# Sensor-Connector.net
KiCad netlist of a schematic drawn in Altium Designer
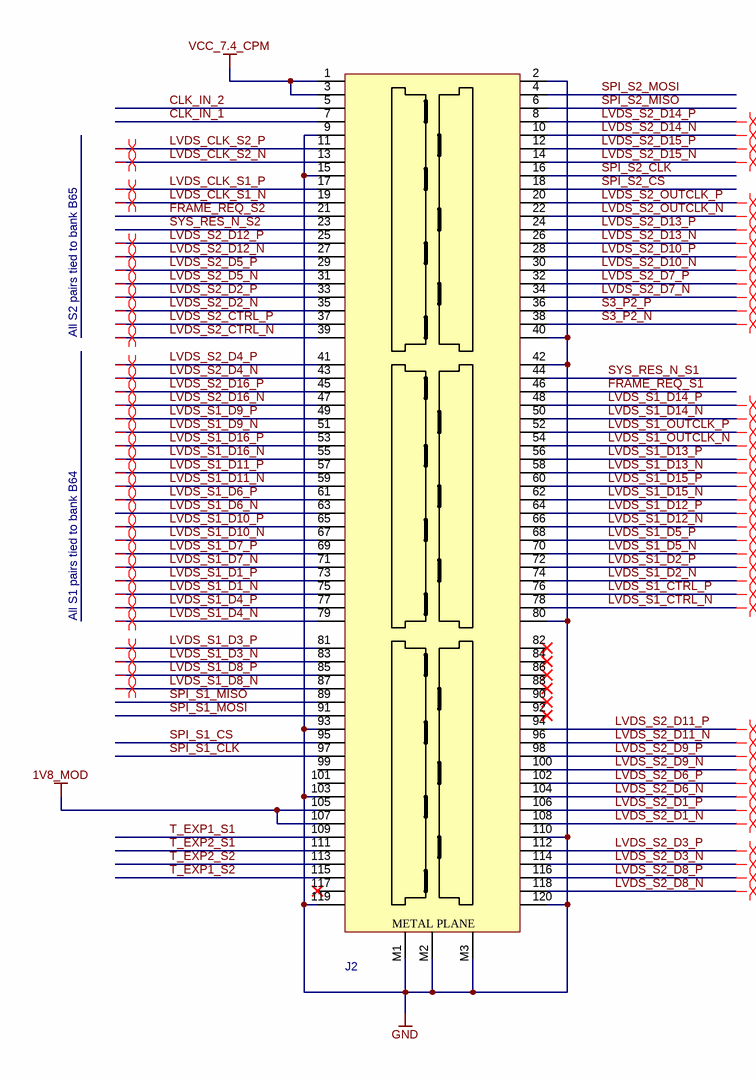
[diagram p0: Sensor-Connector.SchDoc]

(export (version "E")
  (design (tool "Eeschema 10.0.6"))
  (components
    (comp (ref "J2")
      (value "QSE-060-01-L-D-A")
      (footprint "QSE-060-01-L-D-A")
      (fields (field (name "MANUFACTURER") "SAMTEC"))
      (libsource (lib "US-Plus-CPM") (part "QSE-060-01-L-D-A"))
    )
  )
  (nets
    (net (code "1") (name "/CLK_IN_1") (class "Default")
      (node (ref "J2") (pin "7") (pinfunction "7_7") (pintype "passive"))
    )
    (net (code "2") (name "/CLK_IN_2") (class "Default")
      (node (ref "J2") (pin "5") (pinfunction "5_5") (pintype "passive"))
    )
    (net (code "3") (name "/FRAME_REQ_S1") (class "Default")
      (node (ref "J2") (pin "46") (pinfunction "46_46") (pintype "passive"))
    )
    (net (code "4") (name "/FRAME_REQ_S2") (class "Default")
      (node (ref "J2") (pin "21") (pinfunction "21_21") (pintype "passive"))
    )
    (net (code "5") (name "/LVDS_CLK_S1_N") (class "Default")
      (node (ref "J2") (pin "19") (pinfunction "19_19") (pintype "passive"))
    )
    (net (code "6") (name "/LVDS_CLK_S1_P") (class "Default")
      (node (ref "J2") (pin "17") (pinfunction "17_17") (pintype "passive"))
    )
    (net (code "7") (name "/LVDS_CLK_S2_N") (class "Default")
      (node (ref "J2") (pin "13") (pinfunction "13_13") (pintype "passive"))
    )
    (net (code "8") (name "/LVDS_CLK_S2_P") (class "Default")
      (node (ref "J2") (pin "11") (pinfunction "11_11") (pintype "passive"))
    )
    (net (code "9") (name "/LVDS_S1_CTRL_N") (class "Default")
      (node (ref "J2") (pin "78") (pinfunction "78_78") (pintype "passive"))
    )
    (net (code "10") (name "/LVDS_S1_CTRL_P") (class "Default")
      (node (ref "J2") (pin "76") (pinfunction "76_76") (pintype "passive"))
    )
    (net (code "11") (name "/LVDS_S1_D1_N") (class "Default")
      (node (ref "J2") (pin "75") (pinfunction "75_75") (pintype "passive"))
    )
    (net (code "12") (name "/LVDS_S1_D1_P") (class "Default")
      (node (ref "J2") (pin "73") (pinfunction "73_73") (pintype "passive"))
    )
    (net (code "13") (name "/LVDS_S1_D2_N") (class "Default")
      (node (ref "J2") (pin "74") (pinfunction "74_74") (pintype "passive"))
    )
    (net (code "14") (name "/LVDS_S1_D2_P") (class "Default")
      (node (ref "J2") (pin "72") (pinfunction "72_72") (pintype "passive"))
    )
    (net (code "15") (name "/LVDS_S1_D3_N") (class "Default")
      (node (ref "J2") (pin "83") (pinfunction "83_83") (pintype "passive"))
    )
    (net (code "16") (name "/LVDS_S1_D3_P") (class "Default")
      (node (ref "J2") (pin "81") (pinfunction "81_81") (pintype "passive"))
    )
    (net (code "17") (name "/LVDS_S1_D4_N") (class "Default")
      (node (ref "J2") (pin "79") (pinfunction "79_79") (pintype "passive"))
    )
    (net (code "18") (name "/LVDS_S1_D4_P") (class "Default")
      (node (ref "J2") (pin "77") (pinfunction "77_77") (pintype "passive"))
    )
    (net (code "19") (name "/LVDS_S1_D5_N") (class "Default")
      (node (ref "J2") (pin "70") (pinfunction "70_70") (pintype "passive"))
    )
    (net (code "20") (name "/LVDS_S1_D5_P") (class "Default")
      (node (ref "J2") (pin "68") (pinfunction "68_68") (pintype "passive"))
    )
    (net (code "21") (name "/LVDS_S1_D6_N") (class "Default")
      (node (ref "J2") (pin "63") (pinfunction "63_63") (pintype "passive"))
    )
    (net (code "22") (name "/LVDS_S1_D6_P") (class "Default")
      (node (ref "J2") (pin "61") (pinfunction "61_61") (pintype "passive"))
    )
    (net (code "23") (name "/LVDS_S1_D7_N") (class "Default")
      (node (ref "J2") (pin "71") (pinfunction "71_71") (pintype "passive"))
    )
    (net (code "24") (name "/LVDS_S1_D7_P") (class "Default")
      (node (ref "J2") (pin "69") (pinfunction "69_69") (pintype "passive"))
    )
    (net (code "25") (name "/LVDS_S1_D8_N") (class "Default")
      (node (ref "J2") (pin "87") (pinfunction "87_87") (pintype "passive"))
    )
    (net (code "26") (name "/LVDS_S1_D8_P") (class "Default")
      (node (ref "J2") (pin "85") (pinfunction "85_85") (pintype "passive"))
    )
    (net (code "27") (name "/LVDS_S1_D9_N") (class "Default")
      (node (ref "J2") (pin "51") (pinfunction "51_51") (pintype "passive"))
    )
    (net (code "28") (name "/LVDS_S1_D9_P") (class "Default")
      (node (ref "J2") (pin "49") (pinfunction "49_49") (pintype "passive"))
    )
    (net (code "29") (name "/LVDS_S1_D10_N") (class "Default")
      (node (ref "J2") (pin "67") (pinfunction "67_67") (pintype "passive"))
    )
    (net (code "30") (name "/LVDS_S1_D10_P") (class "Default")
      (node (ref "J2") (pin "65") (pinfunction "65_65") (pintype "passive"))
    )
    (net (code "31") (name "/LVDS_S1_D11_N") (class "Default")
      (node (ref "J2") (pin "59") (pinfunction "59_59") (pintype "passive"))
    )
    (net (code "32") (name "/LVDS_S1_D11_P") (class "Default")
      (node (ref "J2") (pin "57") (pinfunction "57_57") (pintype "passive"))
    )
    (net (code "33") (name "/LVDS_S1_D12_N") (class "Default")
      (node (ref "J2") (pin "66") (pinfunction "66_66") (pintype "passive"))
    )
    (net (code "34") (name "/LVDS_S1_D12_P") (class "Default")
      (node (ref "J2") (pin "64") (pinfunction "64_64") (pintype "passive"))
    )
    (net (code "35") (name "/LVDS_S1_D13_N") (class "Default")
      (node (ref "J2") (pin "58") (pinfunction "58_58") (pintype "passive"))
    )
    (net (code "36") (name "/LVDS_S1_D13_P") (class "Default")
      (node (ref "J2") (pin "56") (pinfunction "56_56") (pintype "passive"))
    )
    (net (code "37") (name "/LVDS_S1_D14_N") (class "Default")
      (node (ref "J2") (pin "50") (pinfunction "50_50") (pintype "passive"))
    )
    (net (code "38") (name "/LVDS_S1_D14_P") (class "Default")
      (node (ref "J2") (pin "48") (pinfunction "48_48") (pintype "passive"))
    )
    (net (code "39") (name "/LVDS_S1_D15_N") (class "Default")
      (node (ref "J2") (pin "62") (pinfunction "62_62") (pintype "passive"))
    )
    (net (code "40") (name "/LVDS_S1_D15_P") (class "Default")
      (node (ref "J2") (pin "60") (pinfunction "60_60") (pintype "passive"))
    )
    (net (code "41") (name "/LVDS_S1_D16_N") (class "Default")
      (node (ref "J2") (pin "55") (pinfunction "55_55") (pintype "passive"))
    )
    (net (code "42") (name "/LVDS_S1_D16_P") (class "Default")
      (node (ref "J2") (pin "53") (pinfunction "53_53") (pintype "passive"))
    )
    (net (code "43") (name "/LVDS_S1_OUTCLK_N") (class "Default")
      (node (ref "J2") (pin "54") (pinfunction "54_54") (pintype "passive"))
    )
    (net (code "44") (name "/LVDS_S1_OUTCLK_P") (class "Default")
      (node (ref "J2") (pin "52") (pinfunction "52_52") (pintype "passive"))
    )
    (net (code "45") (name "/LVDS_S2_CTRL_N") (class "Default")
      (node (ref "J2") (pin "39") (pinfunction "39_39") (pintype "passive"))
    )
    (net (code "46") (name "/LVDS_S2_CTRL_P") (class "Default")
      (node (ref "J2") (pin "37") (pinfunction "37_37") (pintype "passive"))
    )
    (net (code "47") (name "/LVDS_S2_D1_N") (class "Default")
      (node (ref "J2") (pin "108") (pinfunction "108_108") (pintype "passive"))
    )
    (net (code "48") (name "/LVDS_S2_D1_P") (class "Default")
      (node (ref "J2") (pin "106") (pinfunction "106_106") (pintype "passive"))
    )
    (net (code "49") (name "/LVDS_S2_D2_N") (class "Default")
      (node (ref "J2") (pin "35") (pinfunction "35_35") (pintype "passive"))
    )
    (net (code "50") (name "/LVDS_S2_D2_P") (class "Default")
      (node (ref "J2") (pin "33") (pinfunction "33_33") (pintype "passive"))
    )
    (net (code "51") (name "/LVDS_S2_D3_N") (class "Default")
      (node (ref "J2") (pin "114") (pinfunction "114_114") (pintype "passive"))
    )
    (net (code "52") (name "/LVDS_S2_D3_P") (class "Default")
      (node (ref "J2") (pin "112") (pinfunction "112_112") (pintype "passive"))
    )
    (net (code "53") (name "/LVDS_S2_D4_N") (class "Default")
      (node (ref "J2") (pin "43") (pinfunction "43_43") (pintype "passive"))
    )
    (net (code "54") (name "/LVDS_S2_D4_P") (class "Default")
      (node (ref "J2") (pin "41") (pinfunction "41_41") (pintype "passive"))
    )
    (net (code "55") (name "/LVDS_S2_D5_N") (class "Default")
      (node (ref "J2") (pin "31") (pinfunction "31_31") (pintype "passive"))
    )
    (net (code "56") (name "/LVDS_S2_D5_P") (class "Default")
      (node (ref "J2") (pin "29") (pinfunction "29_29") (pintype "passive"))
    )
    (net (code "57") (name "/LVDS_S2_D6_N") (class "Default")
      (node (ref "J2") (pin "104") (pinfunction "104_104") (pintype "passive"))
    )
    (net (code "58") (name "/LVDS_S2_D6_P") (class "Default")
      (node (ref "J2") (pin "102") (pinfunction "102_102") (pintype "passive"))
    )
    (net (code "59") (name "/LVDS_S2_D7_N") (class "Default")
      (node (ref "J2") (pin "34") (pinfunction "34_34") (pintype "passive"))
    )
    (net (code "60") (name "/LVDS_S2_D7_P") (class "Default")
      (node (ref "J2") (pin "32") (pinfunction "32_32") (pintype "passive"))
    )
    (net (code "61") (name "/LVDS_S2_D8_N") (class "Default")
      (node (ref "J2") (pin "118") (pinfunction "118_118") (pintype "passive"))
    )
    (net (code "62") (name "/LVDS_S2_D8_P") (class "Default")
      (node (ref "J2") (pin "116") (pinfunction "116_116") (pintype "passive"))
    )
    (net (code "63") (name "/LVDS_S2_D9_N") (class "Default")
      (node (ref "J2") (pin "100") (pinfunction "100_100") (pintype "passive"))
    )
    (net (code "64") (name "/LVDS_S2_D9_P") (class "Default")
      (node (ref "J2") (pin "98") (pinfunction "98_98") (pintype "passive"))
    )
    (net (code "65") (name "/LVDS_S2_D10_N") (class "Default")
      (node (ref "J2") (pin "30") (pinfunction "30_30") (pintype "passive"))
    )
    (net (code "66") (name "/LVDS_S2_D10_P") (class "Default")
      (node (ref "J2") (pin "28") (pinfunction "28_28") (pintype "passive"))
    )
    (net (code "67") (name "/LVDS_S2_D11_N") (class "Default")
      (node (ref "J2") (pin "96") (pinfunction "96_96") (pintype "passive"))
    )
    (net (code "68") (name "/LVDS_S2_D11_P") (class "Default")
      (node (ref "J2") (pin "94") (pinfunction "94_94") (pintype "passive"))
    )
    (net (code "69") (name "/LVDS_S2_D12_N") (class "Default")
      (node (ref "J2") (pin "27") (pinfunction "27_27") (pintype "passive"))
    )
    (net (code "70") (name "/LVDS_S2_D12_P") (class "Default")
      (node (ref "J2") (pin "25") (pinfunction "25_25") (pintype "passive"))
    )
    (net (code "71") (name "/LVDS_S2_D13_N") (class "Default")
      (node (ref "J2") (pin "26") (pinfunction "26_26") (pintype "passive"))
    )
    (net (code "72") (name "/LVDS_S2_D13_P") (class "Default")
      (node (ref "J2") (pin "24") (pinfunction "24_24") (pintype "passive"))
    )
    (net (code "73") (name "/LVDS_S2_D14_N") (class "Default")
      (node (ref "J2") (pin "10") (pinfunction "10_10") (pintype "passive"))
    )
    (net (code "74") (name "/LVDS_S2_D14_P") (class "Default")
      (node (ref "J2") (pin "8") (pinfunction "8_8") (pintype "passive"))
    )
    (net (code "75") (name "/LVDS_S2_D15_N") (class "Default")
      (node (ref "J2") (pin "14") (pinfunction "14_14") (pintype "passive"))
    )
    (net (code "76") (name "/LVDS_S2_D15_P") (class "Default")
      (node (ref "J2") (pin "12") (pinfunction "12_12") (pintype "passive"))
    )
    (net (code "77") (name "/LVDS_S2_D16_N") (class "Default")
      (node (ref "J2") (pin "47") (pinfunction "47_47") (pintype "passive"))
    )
    (net (code "78") (name "/LVDS_S2_D16_P") (class "Default")
      (node (ref "J2") (pin "45") (pinfunction "45_45") (pintype "passive"))
    )
    (net (code "79") (name "/LVDS_S2_OUTCLK_N") (class "Default")
      (node (ref "J2") (pin "22") (pinfunction "22_22") (pintype "passive"))
    )
    (net (code "80") (name "/LVDS_S2_OUTCLK_P") (class "Default")
      (node (ref "J2") (pin "20") (pinfunction "20_20") (pintype "passive"))
    )
    (net (code "81") (name "/S3_P2_N") (class "Default")
      (node (ref "J2") (pin "38") (pinfunction "38_38") (pintype "passive"))
    )
    (net (code "82") (name "/S3_P2_P") (class "Default")
      (node (ref "J2") (pin "36") (pinfunction "36_36") (pintype "passive"))
    )
    (net (code "83") (name "/SPI_S1_CLK") (class "Default")
      (node (ref "J2") (pin "97") (pinfunction "97_97") (pintype "passive"))
    )
    (net (code "84") (name "/SPI_S1_CS") (class "Default")
      (node (ref "J2") (pin "95") (pinfunction "95_95") (pintype "passive"))
    )
    (net (code "85") (name "/SPI_S1_MISO") (class "Default")
      (node (ref "J2") (pin "89") (pinfunction "89_89") (pintype "passive"))
    )
    (net (code "86") (name "/SPI_S1_MOSI") (class "Default")
      (node (ref "J2") (pin "91") (pinfunction "91_91") (pintype "passive"))
    )
    (net (code "87") (name "/SPI_S2_CLK") (class "Default")
      (node (ref "J2") (pin "16") (pinfunction "16_16") (pintype "passive"))
    )
    (net (code "88") (name "/SPI_S2_CS") (class "Default")
      (node (ref "J2") (pin "18") (pinfunction "18_18") (pintype "passive"))
    )
    (net (code "89") (name "/SPI_S2_MISO") (class "Default")
      (node (ref "J2") (pin "6") (pinfunction "6_6") (pintype "passive"))
    )
    (net (code "90") (name "/SPI_S2_MOSI") (class "Default")
      (node (ref "J2") (pin "4") (pinfunction "4_4") (pintype "passive"))
    )
    (net (code "91") (name "/SYS_RES_N_S1") (class "Default")
      (node (ref "J2") (pin "44") (pinfunction "44_44") (pintype "passive"))
    )
    (net (code "92") (name "/SYS_RES_N_S2") (class "Default")
      (node (ref "J2") (pin "23") (pinfunction "23_23") (pintype "passive"))
    )
    (net (code "93") (name "/T_EXP1_S1") (class "Default")
      (node (ref "J2") (pin "109") (pinfunction "109_109") (pintype "passive"))
    )
    (net (code "94") (name "/T_EXP1_S2") (class "Default")
      (node (ref "J2") (pin "115") (pinfunction "115_115") (pintype "passive"))
    )
    (net (code "95") (name "/T_EXP2_S1") (class "Default")
      (node (ref "J2") (pin "111") (pinfunction "111_111") (pintype "passive"))
    )
    (net (code "96") (name "/T_EXP2_S2") (class "Default")
      (node (ref "J2") (pin "113") (pinfunction "113_113") (pintype "passive"))
    )
    (net (code "97") (name "1V8_MOD") (class "Default")
      (node (ref "J2") (pin "105") (pinfunction "105_105") (pintype "passive"))
      (node (ref "J2") (pin "107") (pinfunction "107_107") (pintype "passive"))
    )
    (net (code "98") (name "GND") (class "Default")
      (node (ref "J2") (pin "103") (pinfunction "103_103") (pintype "passive"))
      (node (ref "J2") (pin "110") (pinfunction "110_110") (pintype "passive"))
      (node (ref "J2") (pin "119") (pinfunction "119_119") (pintype "passive"))
      (node (ref "J2") (pin "120") (pinfunction "120_120") (pintype "passive"))
      (node (ref "J2") (pin "15") (pinfunction "15_15") (pintype "passive"))
      (node (ref "J2") (pin "2") (pinfunction "2_2") (pintype "passive"))
      (node (ref "J2") (pin "40") (pinfunction "40_40") (pintype "passive"))
      (node (ref "J2") (pin "42") (pinfunction "42_42") (pintype "passive"))
      (node (ref "J2") (pin "80") (pinfunction "80_80") (pintype "passive"))
      (node (ref "J2") (pin "9") (pinfunction "9_9") (pintype "passive"))
      (node (ref "J2") (pin "93") (pinfunction "93_93") (pintype "passive"))
      (node (ref "J2") (pin "M1") (pinfunction "124_M1") (pintype "passive"))
      (node (ref "J2") (pin "M2") (pinfunction "M2_M2") (pintype "passive"))
      (node (ref "J2") (pin "M3") (pinfunction "M3_M3") (pintype "passive"))
    )
    (net (code "99") (name "VCC_7.4_CPM") (class "Default")
      (node (ref "J2") (pin "1") (pinfunction "1_1") (pintype "passive"))
      (node (ref "J2") (pin "3") (pinfunction "3_3") (pintype "passive"))
    )
    (net (code "100") (name "unconnected-(J2-Pad82)") (class "Default")
      (node (ref "J2") (pin "82") (pinfunction "82_82") (pintype "passive+no_connect"))
    )
    (net (code "101") (name "unconnected-(J2-Pad84)") (class "Default")
      (node (ref "J2") (pin "84") (pinfunction "84_84") (pintype "passive+no_connect"))
    )
    (net (code "102") (name "unconnected-(J2-Pad86)") (class "Default")
      (node (ref "J2") (pin "86") (pinfunction "86_86") (pintype "passive+no_connect"))
    )
    (net (code "103") (name "unconnected-(J2-Pad88)") (class "Default")
      (node (ref "J2") (pin "88") (pinfunction "88_88") (pintype "passive+no_connect"))
    )
    (net (code "104") (name "unconnected-(J2-Pad90)") (class "Default")
      (node (ref "J2") (pin "90") (pinfunction "90_90") (pintype "passive+no_connect"))
    )
    (net (code "105") (name "unconnected-(J2-Pad92)") (class "Default")
      (node (ref "J2") (pin "92") (pinfunction "92_92") (pintype "passive+no_connect"))
    )
    (net (code "106") (name "unconnected-(J2-Pad99)") (class "Default")
      (node (ref "J2") (pin "99") (pinfunction "99_99") (pintype "passive"))
    )
    (net (code "107") (name "unconnected-(J2-Pad101)") (class "Default")
      (node (ref "J2") (pin "101") (pinfunction "101_101") (pintype "passive"))
    )
    (net (code "108") (name "unconnected-(J2-Pad117)") (class "Default")
      (node (ref "J2") (pin "117") (pinfunction "117_117") (pintype "passive+no_connect"))
    )
  )
)
